# iSecure2_0_1.net
KiCad netlist of a schematic drawn in EAGLE
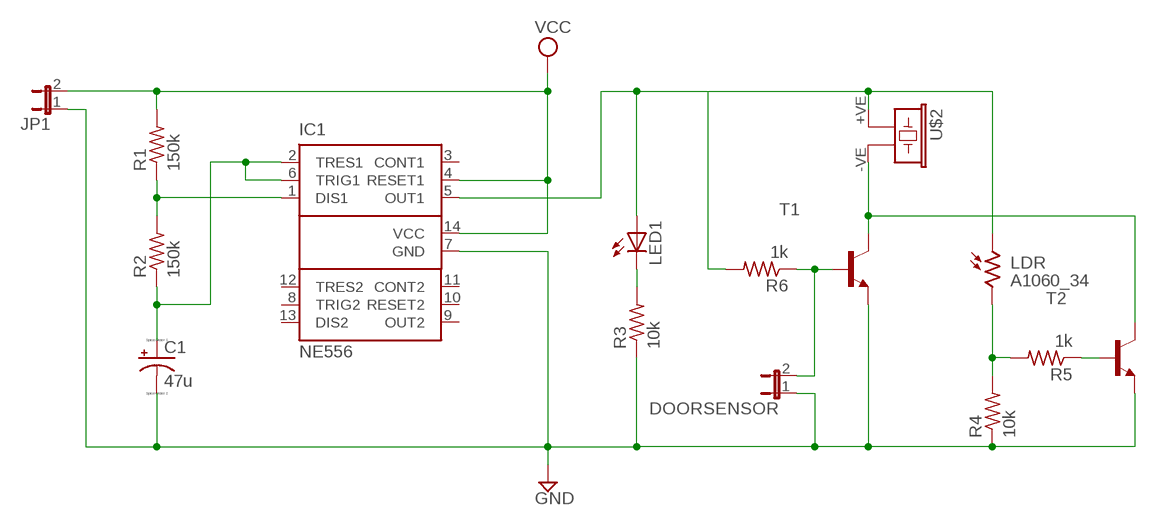
[diagram p0: schematic, sheet 1]

(export (version "E")
  (design (tool "Eeschema 10.0.6"))
  (components
    (comp (ref "C1")
      (value "47u")
      (footprint "eagle-import:TT5D6")
      (libsource (lib "eagle-import") (part "CPOL-USTT6D6"))
    )
    (comp (ref "DOORSENSOR")
      (value "JP1E")
      (footprint "eagle-import:JP1")
      (libsource (lib "eagle-import") (part "JP1E"))
    )
    (comp (ref "IC1")
      (value "NE556")
      (footprint "eagle-import:DIL14")
      (libsource (lib "eagle-import") (part "NE556"))
    )
    (comp (ref "JP1")
      (value "JP1E")
      (footprint "eagle-import:JP1")
      (libsource (lib "eagle-import") (part "JP1E"))
    )
    (comp (ref "LDR")
      (value "A1060_34")
      (footprint "eagle-import:T0-46-A10XX")
      (libsource (lib "eagle-import") (part "A1060_34"))
    )
    (comp (ref "LED1")
      (value "LED5MM")
      (footprint "eagle-import:LED5MM")
      (libsource (lib "eagle-import") (part "LED5MM"))
    )
    (comp (ref "R1")
      (value "150k")
      (footprint "eagle-import:0309_12")
      (libsource (lib "eagle-import") (part "R-US_0309/12"))
    )
    (comp (ref "R2")
      (value "150k")
      (footprint "eagle-import:0309_12")
      (libsource (lib "eagle-import") (part "R-US_0309/12"))
    )
    (comp (ref "R3")
      (value "10k")
      (footprint "eagle-import:0309_12")
      (libsource (lib "eagle-import") (part "R-US_0309/12"))
    )
    (comp (ref "R4")
      (value "10k")
      (footprint "eagle-import:0309_12")
      (libsource (lib "eagle-import") (part "R-US_0309/12"))
    )
    (comp (ref "R5")
      (value "1k")
      (footprint "eagle-import:0309_12")
      (libsource (lib "eagle-import") (part "R-US_0309/12"))
    )
    (comp (ref "R6")
      (value "1k")
      (footprint "eagle-import:0309_12")
      (libsource (lib "eagle-import") (part "R-US_0309/12"))
    )
    (comp (ref "T1")
      (value "2N5550-NPN-TO92-CBE")
      (footprint "eagle-import:TO92-CBE")
      (libsource (lib "eagle-import") (part "-NPN-TO92-CBE2N5550"))
    )
    (comp (ref "T2")
      (value "2N5550-NPN-TO92-CBE")
      (footprint "eagle-import:TO92-CBE")
      (libsource (lib "eagle-import") (part "-NPN-TO92-CBE2N5550"))
    )
    (comp (ref "U$2")
      (value "BUZZER_AI-1440-TWTBUZZER_POLARISED")
      (footprint "eagle-import:DIP762W70P0L1380H750Q2B")
      (libsource (lib "eagle-import") (part "BUZZER_AI-1440-TWTBUZZER_POLARISED"))
    )
  )
  (nets
    (net (code "1") (name "GND") (class "Default")
      (node (ref "C1") (pin "-") (pinfunction "-_-") (pintype "passive"))
      (node (ref "DOORSENSOR") (pin "1") (pinfunction "1_1") (pintype "passive"))
      (node (ref "IC1") (pin "7") (pinfunction "GND_7") (pintype "power_in"))
      (node (ref "JP1") (pin "1") (pinfunction "1_1") (pintype "passive"))
      (node (ref "R3") (pin "1") (pinfunction "1_1") (pintype "passive"))
      (node (ref "R4") (pin "1") (pinfunction "1_1") (pintype "passive"))
      (node (ref "T1") (pin "E") (pinfunction "E_E") (pintype "passive"))
      (node (ref "T2") (pin "E") (pinfunction "E_E") (pintype "passive"))
    )
    (net (code "2") (name "Net-(DOORSENSOR-Pad2)") (class "Default")
      (node (ref "DOORSENSOR") (pin "2") (pinfunction "2_2") (pintype "passive"))
      (node (ref "R6") (pin "1") (pinfunction "1_1") (pintype "passive"))
      (node (ref "T1") (pin "B") (pinfunction "B_B") (pintype "passive"))
    )
    (net (code "3") (name "Net-(IC1-DIS1)") (class "Default")
      (node (ref "IC1") (pin "1") (pinfunction "DIS1_1") (pintype "input"))
      (node (ref "R1") (pin "1") (pinfunction "1_1") (pintype "passive"))
      (node (ref "R2") (pin "2") (pinfunction "2_2") (pintype "passive"))
    )
    (net (code "4") (name "Net-(IC1-OUT1)") (class "Default")
      (node (ref "IC1") (pin "5") (pinfunction "OUT1_5") (pintype "output"))
      (node (ref "LDR") (pin "1") (pinfunction "1_1") (pintype "passive"))
      (node (ref "LED1") (pin "A") (pinfunction "A_A") (pintype "passive"))
      (node (ref "R6") (pin "2") (pinfunction "2_2") (pintype "passive"))
      (node (ref "U$2") (pin "+VE") (pinfunction "1_+VE") (pintype "passive"))
    )
    (net (code "5") (name "Net-(IC1-TRES1)") (class "Default")
      (node (ref "C1") (pin "+") (pinfunction "+_+") (pintype "passive"))
      (node (ref "IC1") (pin "2") (pinfunction "TRES1_2") (pintype "input"))
      (node (ref "IC1") (pin "6") (pinfunction "TRIG1_6") (pintype "input"))
      (node (ref "R2") (pin "1") (pinfunction "1_1") (pintype "passive"))
    )
    (net (code "6") (name "Net-(LDR-Pad2)") (class "Default")
      (node (ref "LDR") (pin "2") (pinfunction "2_2") (pintype "passive"))
      (node (ref "R4") (pin "2") (pinfunction "2_2") (pintype "passive"))
      (node (ref "R5") (pin "2") (pinfunction "2_2") (pintype "passive"))
    )
    (net (code "7") (name "Net-(LED1-C)") (class "Default")
      (node (ref "LED1") (pin "K") (pinfunction "C_K") (pintype "passive"))
      (node (ref "R3") (pin "2") (pinfunction "2_2") (pintype "passive"))
    )
    (net (code "8") (name "Net-(R5-Pad1)") (class "Default")
      (node (ref "R5") (pin "1") (pinfunction "1_1") (pintype "passive"))
      (node (ref "T2") (pin "B") (pinfunction "B_B") (pintype "passive"))
    )
    (net (code "9") (name "Net-(U$2-2)") (class "Default")
      (node (ref "T1") (pin "C") (pinfunction "C_C") (pintype "passive"))
      (node (ref "T2") (pin "C") (pinfunction "C_C") (pintype "passive"))
      (node (ref "U$2") (pin "-VE") (pinfunction "2_-VE") (pintype "passive"))
    )
    (net (code "10") (name "VCC") (class "Default")
      (node (ref "IC1") (pin "14") (pinfunction "VCC_14") (pintype "power_in"))
      (node (ref "IC1") (pin "4") (pinfunction "RESET1_4") (pintype "input"))
      (node (ref "JP1") (pin "2") (pinfunction "2_2") (pintype "passive"))
      (node (ref "R1") (pin "2") (pinfunction "2_2") (pintype "passive"))
    )
    (net (code "11") (name "unconnected-(IC1-CONT1-Pad3)") (class "Default")
      (node (ref "IC1") (pin "3") (pinfunction "CONT1_3") (pintype "input"))
    )
    (net (code "12") (name "unconnected-(IC1-CONT2-Pad11)") (class "Default")
      (node (ref "IC1") (pin "11") (pinfunction "CONT2_11") (pintype "input"))
    )
    (net (code "13") (name "unconnected-(IC1-DIS2-Pad13)") (class "Default")
      (node (ref "IC1") (pin "13") (pinfunction "DIS2_13") (pintype "input"))
    )
    (net (code "14") (name "unconnected-(IC1-OUT2-Pad9)") (class "Default")
      (node (ref "IC1") (pin "9") (pinfunction "OUT2_9") (pintype "output"))
    )
    (net (code "15") (name "unconnected-(IC1-RESET2-Pad10)") (class "Default")
      (node (ref "IC1") (pin "10") (pinfunction "RESET2_10") (pintype "input"))
    )
    (net (code "16") (name "unconnected-(IC1-TRES2-Pad12)") (class "Default")
      (node (ref "IC1") (pin "12") (pinfunction "TRES2_12") (pintype "input"))
    )
    (net (code "17") (name "unconnected-(IC1-TRIG2-Pad8)") (class "Default")
      (node (ref "IC1") (pin "8") (pinfunction "TRIG2_8") (pintype "input"))
    )
  )
)
